# placa_alimentacao.net
KiCad netlist of a schematic drawn in EAGLE
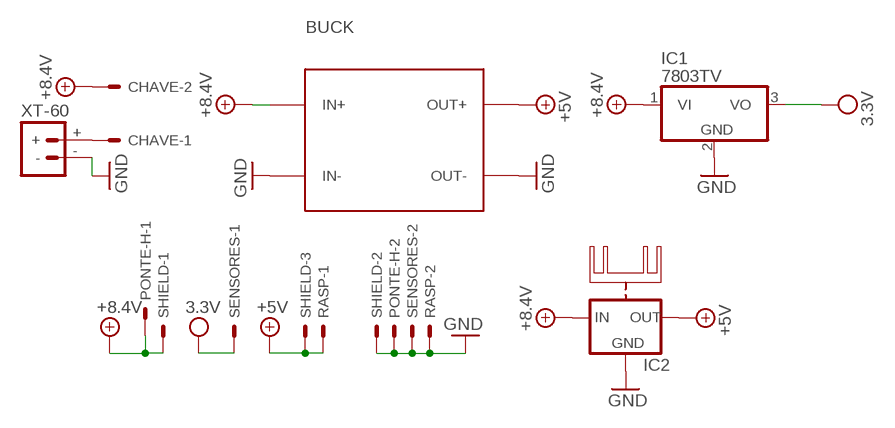
[diagram p0: schematic, sheet 1]

(export (version "E")
  (design (tool "Eeschema 10.0.6"))
  (components
    (comp (ref "BUCK")
      (value "DC-DC-STEP-DOWN-LM2596")
      (footprint "eagle-import:DC-DC-STEP-DOWN-LM2596")
      (libsource (lib "eagle-import") (part "DC-DC-STEP-DOWN-LM2596"))
    )
    (comp (ref "CHAVE")
      (value "CONN_0227-2021")
      (footprint "eagle-import:6410-02")
      (libsource (lib "eagle-import") (part "CONN_0227-2021"))
    )
    (comp (ref "IC1")
      (value "7803TV")
      (footprint "eagle-import:TO220V")
      (libsource (lib "eagle-import") (part "78TV05"))
    )
    (comp (ref "IC2")
      (value "78XXH")
      (footprint "eagle-import:78XXH")
      (libsource (lib "eagle-import") (part "78XXH"))
    )
    (comp (ref "PONTE-H")
      (value "CONN_0227-2021")
      (footprint "eagle-import:6410-02")
      (libsource (lib "eagle-import") (part "CONN_0227-2021"))
    )
    (comp (ref "RASP")
      (value "CONN_0227-2021")
      (footprint "eagle-import:6410-02")
      (libsource (lib "eagle-import") (part "CONN_0227-2021"))
    )
    (comp (ref "SENSORES")
      (value "CONN_0227-2021")
      (footprint "eagle-import:6410-02")
      (libsource (lib "eagle-import") (part "CONN_0227-2021"))
    )
    (comp (ref "SHIELD")
      (value "CONN_0327-2031")
      (footprint "eagle-import:6410-03")
      (libsource (lib "eagle-import") (part "CONN_0327-2031"))
    )
    (comp (ref "XT-60")
      (value "BATTERY_CONNXT60")
      (footprint "eagle-import:XT60")
      (libsource (lib "eagle-import") (part "BATTERY_CONNXT60"))
    )
  )
  (nets
    (net (code "1") (name "+5V") (class "Default")
      (node (ref "BUCK") (pin "OUT+") (pinfunction "OUT+_OUT+") (pintype "bidirectional"))
      (node (ref "IC2") (pin "OUT") (pinfunction "OUT_OUT") (pintype "passive"))
      (node (ref "RASP") (pin "1") (pinfunction "S_1") (pintype "passive"))
      (node (ref "SHIELD") (pin "3") (pinfunction "S_3") (pintype "passive"))
    )
    (net (code "2") (name "+8.4V") (class "Default")
      (node (ref "BUCK") (pin "IN+") (pinfunction "IN+_IN+") (pintype "bidirectional"))
      (node (ref "CHAVE") (pin "2") (pinfunction "S_2") (pintype "passive"))
      (node (ref "IC1") (pin "1") (pinfunction "VI_1") (pintype "input"))
      (node (ref "IC2") (pin "IN") (pinfunction "IN_IN") (pintype "input"))
      (node (ref "PONTE-H") (pin "1") (pinfunction "S_1") (pintype "passive"))
      (node (ref "SHIELD") (pin "1") (pinfunction "S_1") (pintype "passive"))
    )
    (net (code "3") (name "3.3V") (class "Default")
      (node (ref "IC1") (pin "3") (pinfunction "VO_3") (pintype "passive"))
      (node (ref "SENSORES") (pin "1") (pinfunction "S_1") (pintype "passive"))
    )
    (net (code "4") (name "GND") (class "Default")
      (node (ref "BUCK") (pin "IN-") (pinfunction "IN-_IN-") (pintype "bidirectional"))
      (node (ref "BUCK") (pin "OUT-") (pinfunction "OUT-_OUT-") (pintype "bidirectional"))
      (node (ref "IC1") (pin "2") (pinfunction "GND_2") (pintype "passive"))
      (node (ref "IC2") (pin "GND") (pinfunction "GND_GND") (pintype "input"))
      (node (ref "PONTE-H") (pin "2") (pinfunction "S_2") (pintype "passive"))
      (node (ref "RASP") (pin "2") (pinfunction "S_2") (pintype "passive"))
      (node (ref "SENSORES") (pin "2") (pinfunction "S_2") (pintype "passive"))
      (node (ref "SHIELD") (pin "2") (pinfunction "S_2") (pintype "passive"))
      (node (ref "XT-60") (pin "-") (pinfunction "-_-") (pintype "passive"))
    )
    (net (code "5") (name "Net-(CHAVEA-S)") (class "Default")
      (node (ref "CHAVE") (pin "1") (pinfunction "S_1") (pintype "passive"))
      (node (ref "XT-60") (pin "+") (pinfunction "+_+") (pintype "passive"))
    )
  )
)
